# relay_latch_circuit_v2.net
KiCad netlist of a schematic drawn in Altium Designer
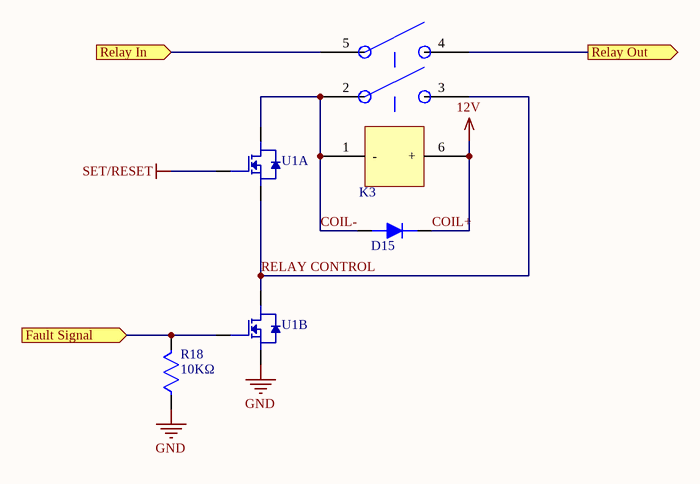
[diagram p0: relay_latch_circuit_v2.SchDoc]

(export (version "E")
  (design (tool "Eeschema 10.0.6"))
  (components
    (comp (ref "D15")
      (value "SD560BTR")
      (footprint "DIODE")
      (description "DIODE GEN PURP 600V 5A SMB")
      (fields (field (name "MANUFACTURER") "SMC"))
      (libsource (lib "sdc_prech_schlib") (part "SD560BTR"))
    )
    (comp (ref "K3")
      (value "5-1419124-6")
      (footprint "DPST SDC RELAY")
      (description "General Purpose Relay, Osa Series, Power, Non Latching, Dpst-No, 12 Vdc, 3 A Rohs Compliant: Yes")
      (fields (field (name "MANUFACTURER") "TE Connectivity"))
      (libsource (lib "sdc_prech_schlib") (part "5-1419124-6"))
    )
    (comp (ref "R18")
      (value "10KΩ")
      (footprint "RESISTOR CRCW0603")
      (description "RES SMD 10K OHM 1% 1/10W 0603")
      (fields
        (field (name "MANUFACTURER") "Vishay")
        (field (name "MANUFACTURER PART NUMBER") "CRCW060310K0FKEA")
      )
      (libsource (lib "sdc_prech_schlib") (part "CRCW060310K0FKEA"))
    )
    (comp (ref "U1")
      (value "SSM6N7002CFU,LF")
      (footprint "N-MOSFET (2 FETS)")
      (description "MOSFET 2N-CH 60V 0.17A US6")
      (fields (field (name "MANUFACTURER") "Toshiba"))
      (libsource (lib "sdc_prech_schlib") (part "SSM6N7002CFU,LF"))
    )
  )
  (nets
    (net (code "1") (name "/COIL-") (class "Default")
      (node (ref "D15") (pin "1") (pinfunction "1_1") (pintype "passive"))
      (node (ref "K3") (pin "1") (pinfunction "-_1") (pintype "passive"))
      (node (ref "K3") (pin "2") (pintype "passive"))
      (node (ref "U1") (pin "6") (pinfunction "D1_6") (pintype "passive"))
    )
    (net (code "2") (name "/Fault Signal") (class "Default")
      (node (ref "R18") (pin "2") (pinfunction "2_2") (pintype "passive"))
      (node (ref "U1") (pin "5") (pinfunction "G2_5") (pintype "passive"))
    )
    (net (code "3") (name "/RELAY CONTROL") (class "Default")
      (node (ref "K3") (pin "3") (pintype "passive"))
      (node (ref "U1") (pin "1") (pinfunction "S1_1") (pintype "passive"))
      (node (ref "U1") (pin "3") (pinfunction "D2_3") (pintype "passive"))
    )
    (net (code "4") (name "/Relay In") (class "Default") (node (ref "K3") (pin "5") (pintype "passive")))
    (net (code "5") (name "/Relay Out") (class "Default") (node (ref "K3") (pin "4") (pintype "passive")))
    (net (code "6") (name "12V") (class "Default")
      (node (ref "D15") (pin "2") (pinfunction "2_2") (pintype "passive"))
      (node (ref "K3") (pin "6") (pinfunction "+_6") (pintype "passive"))
    )
    (net (code "7") (name "GND") (class "Default")
      (node (ref "R18") (pin "1") (pinfunction "1_1") (pintype "passive"))
      (node (ref "U1") (pin "4") (pinfunction "S2_4") (pintype "passive"))
    )
    (net (code "8") (name "SET{slash}RESET") (class "Default")
      (node (ref "U1") (pin "2") (pinfunction "G1_2") (pintype "passive"))
    )
  )
)
